# SmartMDCPrint.net
KiCad netlist of a schematic drawn in EAGLE
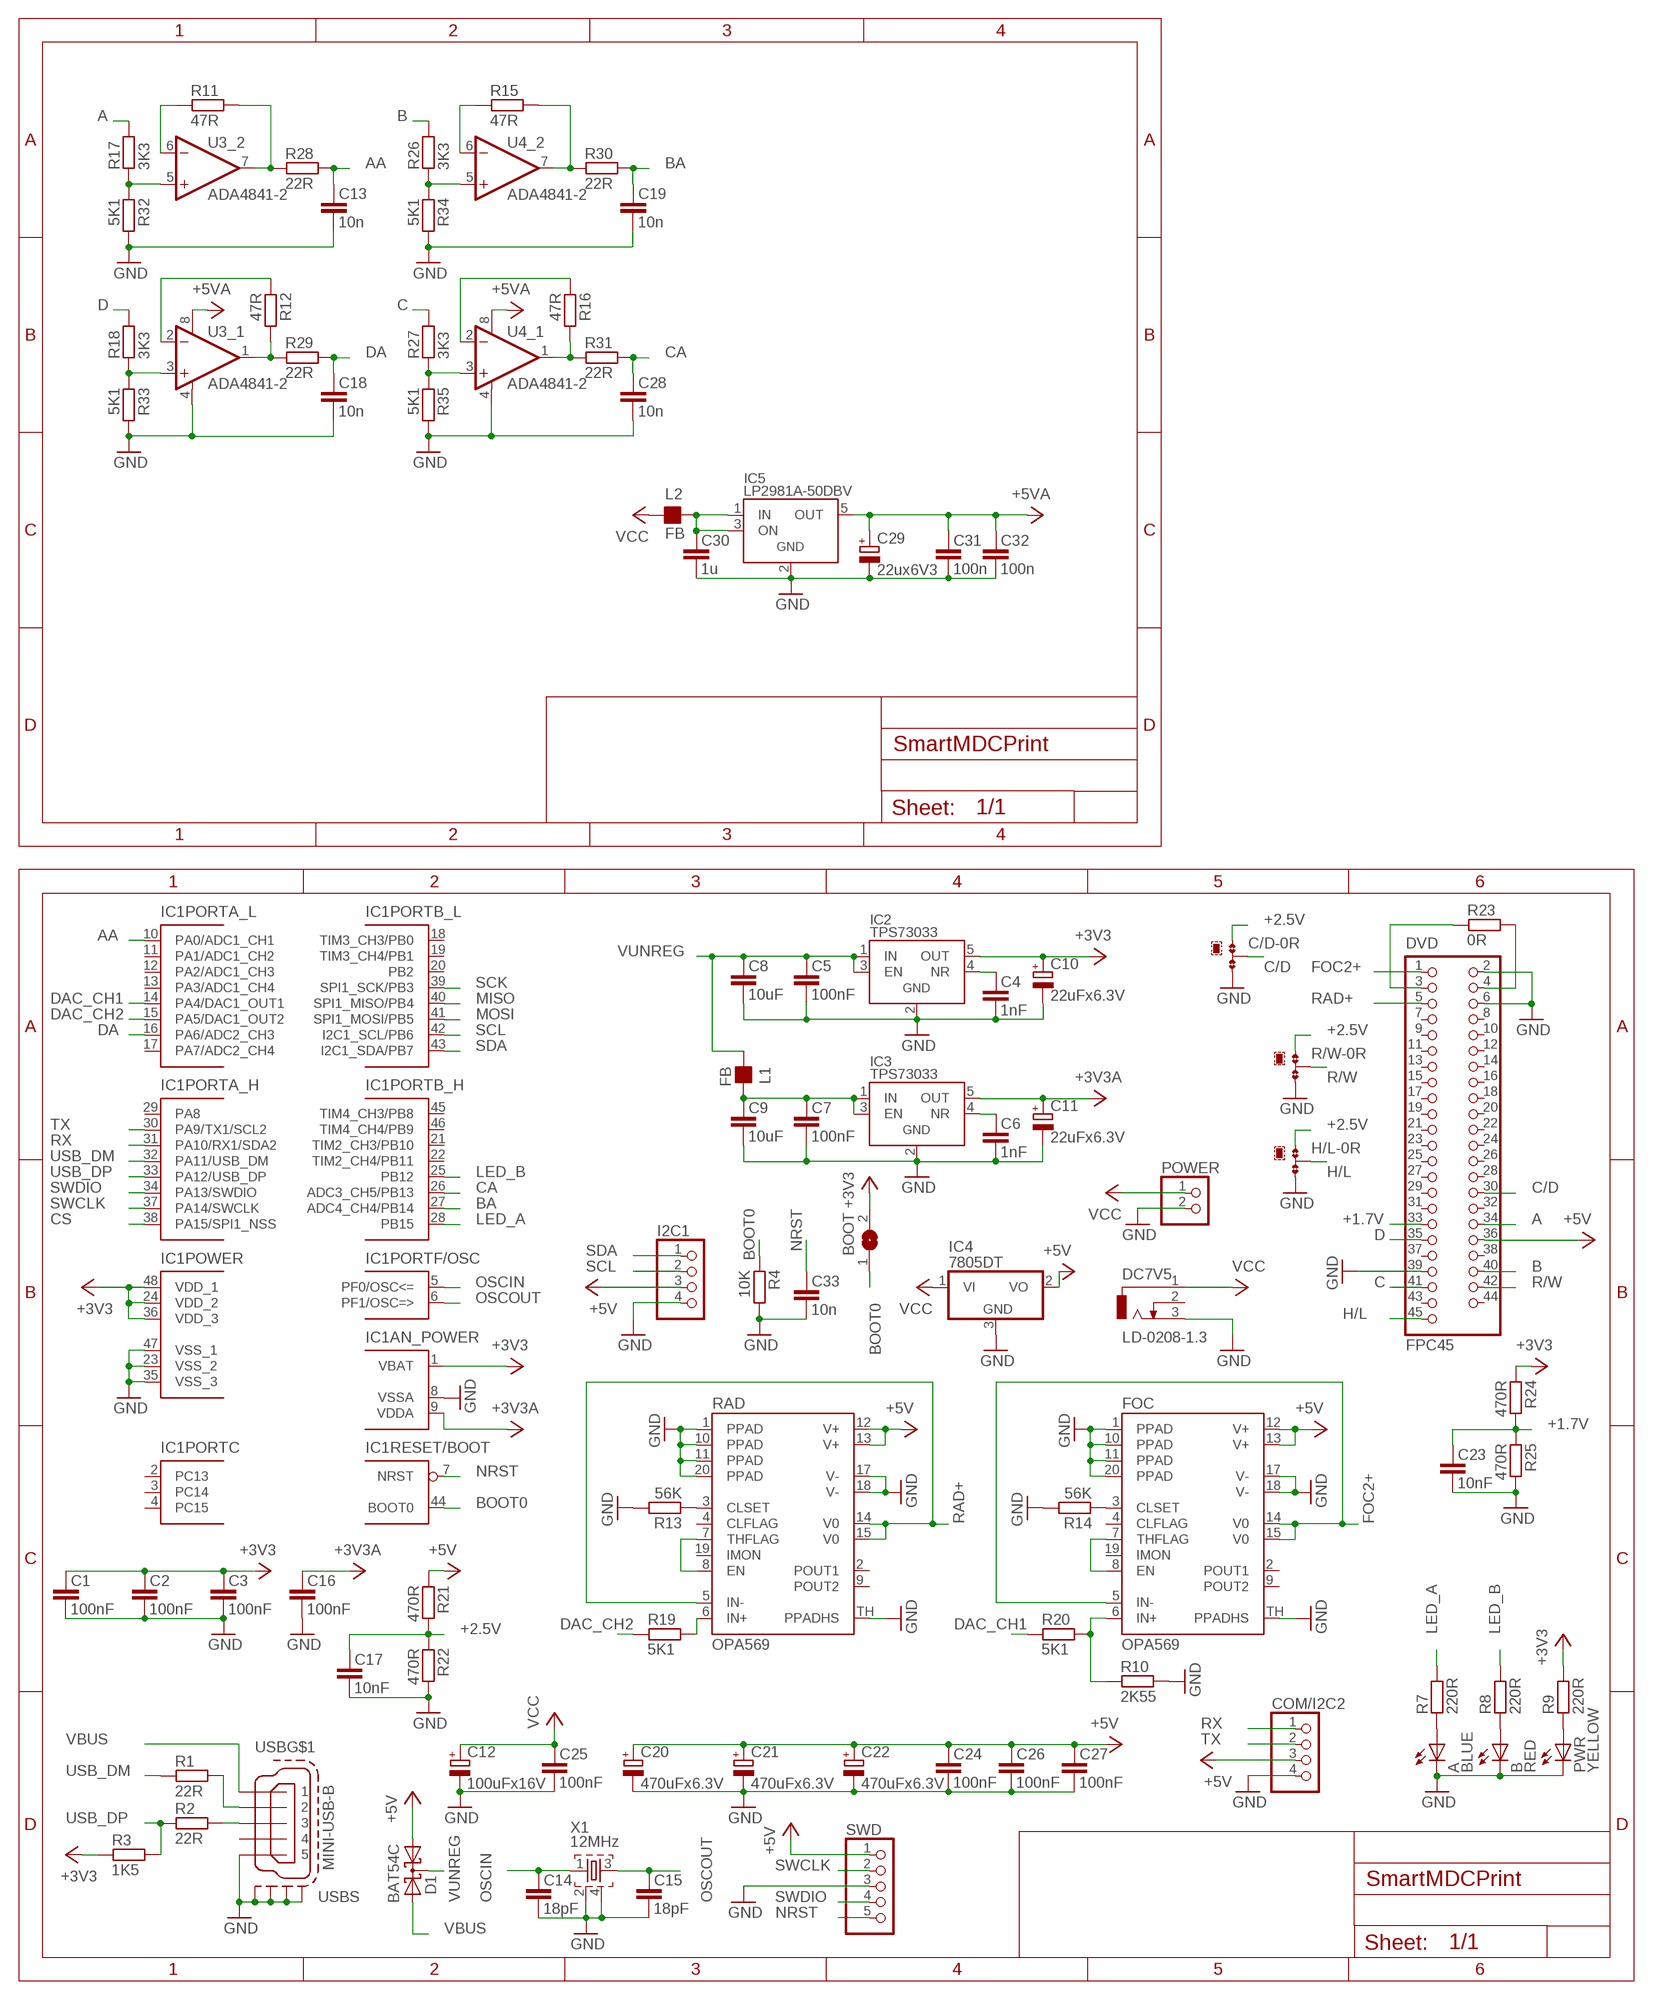
[diagram p0: schematic, sheet 1]

(export (version "E")
  (design (tool "Eeschema 10.0.6"))
  (components
    (comp (ref "A")
      (value "BLUE")
      (footprint "eagle-import:CHIPLED_0805")
      (libsource (lib "eagle-import") (part "LEDCHIPLED_0805"))
    )
    (comp (ref "B")
      (value "RED")
      (footprint "eagle-import:CHIPLED_0805")
      (libsource (lib "eagle-import") (part "LEDCHIPLED_0805"))
    )
    (comp (ref "BOOT")
      (value "SJ")
      (footprint "eagle-import:SJ")
      (libsource (lib "eagle-import") (part "SJ"))
    )
    (comp (ref "C/D")
      (value "0R-JUMPA")
      (footprint "eagle-import:A0R-JMP")
      (libsource (lib "eagle-import") (part "0R-JUMPA"))
    )
    (comp (ref "C1")
      (value "100nF")
      (footprint "eagle-import:C0603G")
      (libsource (lib "eagle-import") (part "C_EU_C0603G"))
    )
    (comp (ref "C2")
      (value "100nF")
      (footprint "eagle-import:C0603G")
      (libsource (lib "eagle-import") (part "C_EU_C0603G"))
    )
    (comp (ref "C3")
      (value "100nF")
      (footprint "eagle-import:C0603G")
      (libsource (lib "eagle-import") (part "C_EU_C0603G"))
    )
    (comp (ref "C4")
      (value "1nF")
      (footprint "eagle-import:C0603G")
      (libsource (lib "eagle-import") (part "C_EU_C0603G"))
    )
    (comp (ref "C5")
      (value "100nF")
      (footprint "eagle-import:C0603G")
      (libsource (lib "eagle-import") (part "C_EU_C0603G"))
    )
    (comp (ref "C6")
      (value "1nF")
      (footprint "eagle-import:C0603G")
      (libsource (lib "eagle-import") (part "C_EU_C0603G"))
    )
    (comp (ref "C7")
      (value "100nF")
      (footprint "eagle-import:C0603G")
      (libsource (lib "eagle-import") (part "C_EU_C0603G"))
    )
    (comp (ref "C8")
      (value "10uF")
      (footprint "eagle-import:C0805")
      (libsource (lib "eagle-import") (part "C_EU_C0805"))
    )
    (comp (ref "C9")
      (value "10uF")
      (footprint "eagle-import:C0805")
      (libsource (lib "eagle-import") (part "C_EU_C0805"))
    )
    (comp (ref "C10")
      (value "22uFx6.3V")
      (footprint "eagle-import:SMC_A")
      (libsource (lib "eagle-import") (part "CPOL-EUSMCA"))
    )
    (comp (ref "C11")
      (value "22uFx6.3V")
      (footprint "eagle-import:SMC_A")
      (libsource (lib "eagle-import") (part "CPOL-EUSMCA"))
    )
    (comp (ref "C12")
      (value "100uFx16V")
      (footprint "eagle-import:E2,5-7")
      (libsource (lib "eagle-import") (part "CPOL-EUE2.5-7"))
    )
    (comp (ref "C13")
      (value "10n")
      (footprint "eagle-import:C0603G")
      (libsource (lib "eagle-import") (part "C_EU_C0603G"))
    )
    (comp (ref "C14")
      (value "18pF")
      (footprint "eagle-import:C0603G")
      (libsource (lib "eagle-import") (part "C_EU_C0603G"))
    )
    (comp (ref "C15")
      (value "18pF")
      (footprint "eagle-import:C0603G")
      (libsource (lib "eagle-import") (part "C_EU_C0603G"))
    )
    (comp (ref "C16")
      (value "100nF")
      (footprint "eagle-import:C0603G")
      (libsource (lib "eagle-import") (part "C_EU_C0603G"))
    )
    (comp (ref "C17")
      (value "10nF")
      (footprint "eagle-import:C0603G")
      (libsource (lib "eagle-import") (part "C_EU_C0603G"))
    )
    (comp (ref "C18")
      (value "10n")
      (footprint "eagle-import:C0603G")
      (libsource (lib "eagle-import") (part "C_EU_C0603G"))
    )
    (comp (ref "C19")
      (value "10n")
      (footprint "eagle-import:C0603G")
      (libsource (lib "eagle-import") (part "C_EU_C0603G"))
    )
    (comp (ref "C20")
      (value "470uFx6.3V")
      (footprint "eagle-import:SMC_D")
      (libsource (lib "eagle-import") (part "CPOL-EUSMCD"))
    )
    (comp (ref "C21")
      (value "470uFx6.3V")
      (footprint "eagle-import:SMC_D")
      (libsource (lib "eagle-import") (part "CPOL-EUSMCD"))
    )
    (comp (ref "C22")
      (value "470uFx6.3V")
      (footprint "eagle-import:SMC_D")
      (libsource (lib "eagle-import") (part "CPOL-EUSMCD"))
    )
    (comp (ref "C23")
      (value "10nF")
      (footprint "eagle-import:C0603G")
      (libsource (lib "eagle-import") (part "C_EU_C0603G"))
    )
    (comp (ref "C24")
      (value "100nF")
      (footprint "eagle-import:C0603G")
      (libsource (lib "eagle-import") (part "C_EU_C0603G"))
    )
    (comp (ref "C25")
      (value "100nF")
      (footprint "eagle-import:C0603G")
      (libsource (lib "eagle-import") (part "C_EU_C0603G"))
    )
    (comp (ref "C26")
      (value "100nF")
      (footprint "eagle-import:C0603G")
      (libsource (lib "eagle-import") (part "C_EU_C0603G"))
    )
    (comp (ref "C27")
      (value "100nF")
      (footprint "eagle-import:C0603G")
      (libsource (lib "eagle-import") (part "C_EU_C0603G"))
    )
    (comp (ref "C28")
      (value "10n")
      (footprint "eagle-import:C0603G")
      (libsource (lib "eagle-import") (part "C_EU_C0603G"))
    )
    (comp (ref "C29")
      (value "22ux6V3")
      (footprint "eagle-import:SMC_A")
      (libsource (lib "eagle-import") (part "CPOL-EUSMCA"))
    )
    (comp (ref "C30")
      (value "1u")
      (footprint "eagle-import:C0603G")
      (libsource (lib "eagle-import") (part "C_EU_C0603G"))
    )
    (comp (ref "C31")
      (value "100n")
      (footprint "eagle-import:C0603G")
      (libsource (lib "eagle-import") (part "C_EU_C0603G"))
    )
    (comp (ref "C32")
      (value "100n")
      (footprint "eagle-import:C0603G")
      (libsource (lib "eagle-import") (part "C_EU_C0603G"))
    )
    (comp (ref "C33")
      (value "10n")
      (footprint "eagle-import:C0603G")
      (libsource (lib "eagle-import") (part "C_EU_C0603G"))
    )
    (comp (ref "COM/I2C2")
      (value "PINHD-1X4")
      (footprint "eagle-import:1X04")
      (libsource (lib "eagle-import") (part "PINHD-1X4"))
    )
    (comp (ref "D1")
      (value "BAT54C")
      (footprint "eagle-import:SOT23")
      (libsource (lib "eagle-import") (part "BAT54C"))
    )
    (comp (ref "DC7V5")
      (value "LD-0208-1.3")
      (footprint "eagle-import:LD-0208")
      (libsource (lib "eagle-import") (part "LD-0208-1.3"))
    )
    (comp (ref "DVD")
      (value "FPC45")
      (footprint "eagle-import:FPC45")
      (libsource (lib "eagle-import") (part "CON-FPC45"))
    )
    (comp (ref "FOC")
      (value "OPA569")
      (footprint "eagle-import:SO-20")
      (libsource (lib "eagle-import") (part "OPA569"))
    )
    (comp (ref "H/L")
      (value "0R-JUMPA")
      (footprint "eagle-import:A0R-JMP")
      (libsource (lib "eagle-import") (part "0R-JUMPA"))
    )
    (comp (ref "I2C1")
      (value "PINHD-1X4")
      (footprint "eagle-import:1X04")
      (libsource (lib "eagle-import") (part "PINHD-1X4"))
    )
    (comp (ref "IC1")
      (value "STM32F303CCT6")
      (footprint "eagle-import:LQFP48")
      (libsource (lib "eagle-import") (part "STM32F303CXT6"))
    )
    (comp (ref "IC2")
      (value "TPS73033")
      (footprint "eagle-import:SOT23-5")
      (libsource (lib "eagle-import") (part "TPS769XX"))
    )
    (comp (ref "IC3")
      (value "TPS73033")
      (footprint "eagle-import:SOT23-5")
      (libsource (lib "eagle-import") (part "TPS769XX"))
    )
    (comp (ref "IC4")
      (value "7805DT")
      (footprint "eagle-import:TO252")
      (libsource (lib "eagle-import") (part "78DT05"))
    )
    (comp (ref "IC5")
      (value "LP2981A-50DBV")
      (footprint "eagle-import:SOT23-5")
      (libsource (lib "eagle-import") (part "LP2981A-50DBV"))
    )
    (comp (ref "L1")
      (value "FB")
      (footprint "eagle-import:L0603")
      (libsource (lib "eagle-import") (part "FB_0603"))
    )
    (comp (ref "L2")
      (value "FB")
      (footprint "eagle-import:L0603")
      (libsource (lib "eagle-import") (part "FB_0603"))
    )
    (comp (ref "POWER")
      (value "PINHD-1X2")
      (footprint "eagle-import:1X02")
      (libsource (lib "eagle-import") (part "PINHD-1X2"))
    )
    (comp (ref "PWR")
      (value "YELLOW")
      (footprint "eagle-import:CHIPLED_0805")
      (libsource (lib "eagle-import") (part "LEDCHIPLED_0805"))
    )
    (comp (ref "R/W")
      (value "0R-JUMPA")
      (footprint "eagle-import:A0R-JMP")
      (libsource (lib "eagle-import") (part "0R-JUMPA"))
    )
    (comp (ref "R1")
      (value "22R")
      (footprint "eagle-import:R0603")
      (libsource (lib "eagle-import") (part "R_EU_R0603"))
    )
    (comp (ref "R2")
      (value "22R")
      (footprint "eagle-import:R0603")
      (libsource (lib "eagle-import") (part "R_EU_R0603"))
    )
    (comp (ref "R3")
      (value "1K5")
      (footprint "eagle-import:R0603")
      (libsource (lib "eagle-import") (part "R_EU_R0603"))
    )
    (comp (ref "R4")
      (value "10K")
      (footprint "eagle-import:R0603G")
      (libsource (lib "eagle-import") (part "R_EU_R0603G"))
    )
    (comp (ref "R7")
      (value "220R")
      (footprint "eagle-import:R0603")
      (libsource (lib "eagle-import") (part "R_EU_R0603"))
    )
    (comp (ref "R8")
      (value "220R")
      (footprint "eagle-import:R0603")
      (libsource (lib "eagle-import") (part "R_EU_R0603"))
    )
    (comp (ref "R9")
      (value "220R")
      (footprint "eagle-import:R0603")
      (libsource (lib "eagle-import") (part "R_EU_R0603"))
    )
    (comp (ref "R10")
      (value "2K55")
      (footprint "eagle-import:R0603G")
      (libsource (lib "eagle-import") (part "R_EU_R0603G"))
    )
    (comp (ref "R11")
      (value "47R")
      (footprint "eagle-import:R0603")
      (libsource (lib "eagle-import") (part "R_EU_R0603"))
    )
    (comp (ref "R12")
      (value "47R")
      (footprint "eagle-import:R0603")
      (libsource (lib "eagle-import") (part "R_EU_R0603"))
    )
    (comp (ref "R13")
      (value "56K")
      (footprint "eagle-import:R0603G")
      (libsource (lib "eagle-import") (part "R_EU_R0603G"))
    )
    (comp (ref "R14")
      (value "56K")
      (footprint "eagle-import:R0603G")
      (libsource (lib "eagle-import") (part "R_EU_R0603G"))
    )
    (comp (ref "R15")
      (value "47R")
      (footprint "eagle-import:R0603")
      (libsource (lib "eagle-import") (part "R_EU_R0603"))
    )
    (comp (ref "R16")
      (value "47R")
      (footprint "eagle-import:R0603")
      (libsource (lib "eagle-import") (part "R_EU_R0603"))
    )
    (comp (ref "R17")
      (value "3K3")
      (footprint "eagle-import:R0603")
      (libsource (lib "eagle-import") (part "R_EU_R0603"))
    )
    (comp (ref "R18")
      (value "3K3")
      (footprint "eagle-import:R0603")
      (libsource (lib "eagle-import") (part "R_EU_R0603"))
    )
    (comp (ref "R19")
      (value "5K1")
      (footprint "eagle-import:R0603")
      (libsource (lib "eagle-import") (part "R_EU_R0603"))
    )
    (comp (ref "R20")
      (value "5K1")
      (footprint "eagle-import:R0603")
      (libsource (lib "eagle-import") (part "R_EU_R0603"))
    )
    (comp (ref "R21")
      (value "470R")
      (footprint "eagle-import:R0603")
      (libsource (lib "eagle-import") (part "R_EU_R0603"))
    )
    (comp (ref "R22")
      (value "470R")
      (footprint "eagle-import:R0603G")
      (libsource (lib "eagle-import") (part "R_EU_R0603G"))
    )
    (comp (ref "R23")
      (value "0R")
      (footprint "eagle-import:R0603")
      (libsource (lib "eagle-import") (part "R_EU_R0603"))
    )
    (comp (ref "R24")
      (value "470R")
      (footprint "eagle-import:R0603")
      (libsource (lib "eagle-import") (part "R_EU_R0603"))
    )
    (comp (ref "R25")
      (value "470R")
      (footprint "eagle-import:R0603G")
      (libsource (lib "eagle-import") (part "R_EU_R0603G"))
    )
    (comp (ref "R26")
      (value "3K3")
      (footprint "eagle-import:R0603")
      (libsource (lib "eagle-import") (part "R_EU_R0603"))
    )
    (comp (ref "R27")
      (value "3K3")
      (footprint "eagle-import:R0603")
      (libsource (lib "eagle-import") (part "R_EU_R0603"))
    )
    (comp (ref "R28")
      (value "22R")
      (footprint "eagle-import:R0603")
      (libsource (lib "eagle-import") (part "R_EU_R0603"))
    )
    (comp (ref "R29")
      (value "22R")
      (footprint "eagle-import:R0603")
      (libsource (lib "eagle-import") (part "R_EU_R0603"))
    )
    (comp (ref "R30")
      (value "22R")
      (footprint "eagle-import:R0603")
      (libsource (lib "eagle-import") (part "R_EU_R0603"))
    )
    (comp (ref "R31")
      (value "22R")
      (footprint "eagle-import:R0603")
      (libsource (lib "eagle-import") (part "R_EU_R0603"))
    )
    (comp (ref "R32")
      (value "5K1")
      (footprint "eagle-import:R0603G")
      (libsource (lib "eagle-import") (part "R_EU_R0603G"))
    )
    (comp (ref "R33")
      (value "5K1")
      (footprint "eagle-import:R0603G")
      (libsource (lib "eagle-import") (part "R_EU_R0603G"))
    )
    (comp (ref "R34")
      (value "5K1")
      (footprint "eagle-import:R0603G")
      (libsource (lib "eagle-import") (part "R_EU_R0603G"))
    )
    (comp (ref "R35")
      (value "5K1")
      (footprint "eagle-import:R0603G")
      (libsource (lib "eagle-import") (part "R_EU_R0603G"))
    )
    (comp (ref "RAD")
      (value "OPA569")
      (footprint "eagle-import:SO-20")
      (libsource (lib "eagle-import") (part "OPA569"))
    )
    (comp (ref "SWD")
      (value "PINHD-1X5")
      (footprint "eagle-import:1X05")
      (libsource (lib "eagle-import") (part "PINHD-1X5"))
    )
    (comp (ref "U3")
      (value "ADA4841-2")
      (footprint "eagle-import:SOIC-8")
      (libsource (lib "eagle-import") (part "ADA4841-2"))
    )
    (comp (ref "U4")
      (value "ADA4841-2")
      (footprint "eagle-import:SOIC-8")
      (libsource (lib "eagle-import") (part "ADA4841-2"))
    )
    (comp (ref "USB")
      (value "MINI-USB-B")
      (footprint "eagle-import:32005-201")
      (libsource (lib "eagle-import") (part "MINI-USB-SCHIELD-32005-201"))
    )
    (comp (ref "X1")
      (value "12MHz")
      (footprint "eagle-import:ABMM2")
      (libsource (lib "eagle-import") (part "ABMM2"))
    )
  )
  (nets
    (net (code "1") (name "+3V3") (class "Default")
      (node (ref "BOOT") (pin "2") (pinfunction "2_2") (pintype "passive"))
      (node (ref "C1") (pin "1") (pinfunction "1_1") (pintype "passive"))
      (node (ref "C10") (pin "+") (pinfunction "+_+") (pintype "passive"))
      (node (ref "C2") (pin "1") (pinfunction "1_1") (pintype "passive"))
      (node (ref "C3") (pin "1") (pinfunction "1_1") (pintype "passive"))
      (node (ref "IC1") (pin "1") (pinfunction "VBAT_1") (pintype "power_in"))
      (node (ref "IC1") (pin "24") (pinfunction "VDD_2_24") (pintype "power_in"))
      (node (ref "IC1") (pin "36") (pinfunction "VDD_3_36") (pintype "power_in"))
      (node (ref "IC1") (pin "48") (pinfunction "VDD_1_48") (pintype "power_in"))
      (node (ref "IC2") (pin "5") (pinfunction "OUT_5") (pintype "power_in"))
      (node (ref "R24") (pin "1") (pinfunction "1_1") (pintype "passive"))
      (node (ref "R3") (pin "1") (pinfunction "1_1") (pintype "passive"))
      (node (ref "R9") (pin "2") (pinfunction "2_2") (pintype "passive"))
    )
    (net (code "2") (name "+3V3A") (class "Default")
      (node (ref "C11") (pin "+") (pinfunction "+_+") (pintype "passive"))
      (node (ref "C16") (pin "1") (pinfunction "1_1") (pintype "passive"))
      (node (ref "IC1") (pin "9") (pinfunction "VDDA_9") (pintype "power_in"))
      (node (ref "IC3") (pin "5") (pinfunction "OUT_5") (pintype "power_in"))
    )
    (net (code "3") (name "+5V") (class "Default")
      (node (ref "C20") (pin "+") (pinfunction "+_+") (pintype "passive"))
      (node (ref "C21") (pin "+") (pinfunction "+_+") (pintype "passive"))
      (node (ref "C22") (pin "+") (pinfunction "+_+") (pintype "passive"))
      (node (ref "C24") (pin "1") (pinfunction "1_1") (pintype "passive"))
      (node (ref "C26") (pin "1") (pinfunction "1_1") (pintype "passive"))
      (node (ref "C27") (pin "1") (pinfunction "1_1") (pintype "passive"))
      (node (ref "COM/I2C2") (pin "3") (pinfunction "3_3") (pintype "passive"))
      (node (ref "D1") (pin "1") (pinfunction "A1_1") (pintype "passive"))
      (node (ref "DVD") (pin "36") (pinfunction "36_36") (pintype "passive"))
      (node (ref "FOC") (pin "12") (pinfunction "V+_12") (pintype "bidirectional"))
      (node (ref "FOC") (pin "13") (pinfunction "V+_13") (pintype "bidirectional"))
      (node (ref "I2C1") (pin "3") (pinfunction "3_3") (pintype "passive"))
      (node (ref "IC4") (pin "2") (pinfunction "VO_2") (pintype "passive"))
      (node (ref "R21") (pin "1") (pinfunction "1_1") (pintype "passive"))
      (node (ref "RAD") (pin "12") (pinfunction "V+_12") (pintype "bidirectional"))
      (node (ref "RAD") (pin "13") (pinfunction "V+_13") (pintype "bidirectional"))
      (node (ref "SWD") (pin "1") (pinfunction "1_1") (pintype "passive"))
    )
    (net (code "4") (name "+5VA") (class "Default")
      (node (ref "C29") (pin "+") (pinfunction "+_+") (pintype "passive"))
      (node (ref "C31") (pin "1") (pinfunction "1_1") (pintype "passive"))
      (node (ref "C32") (pin "1") (pinfunction "1_1") (pintype "passive"))
      (node (ref "IC5") (pin "5") (pinfunction "OUT_5") (pintype "power_in"))
      (node (ref "U3") (pin "8") (pinfunction "V+_8") (pintype "power_in"))
      (node (ref "U4") (pin "8") (pinfunction "V+_8") (pintype "power_in"))
    )
    (net (code "5") (name "/+1.7V") (class "Default")
      (node (ref "C23") (pin "1") (pinfunction "1_1") (pintype "passive"))
      (node (ref "DVD") (pin "33") (pinfunction "33_33") (pintype "passive"))
      (node (ref "R24") (pin "2") (pinfunction "2_2") (pintype "passive"))
      (node (ref "R25") (pin "1") (pinfunction "1_1") (pintype "passive"))
    )
    (net (code "6") (name "/+2.5V") (class "Default")
      (node (ref "C/D") (pin "1") (pinfunction "1_1") (pintype "passive"))
      (node (ref "C17") (pin "1") (pinfunction "1_1") (pintype "passive"))
      (node (ref "H/L") (pin "1") (pinfunction "1_1") (pintype "passive"))
      (node (ref "R/W") (pin "1") (pinfunction "1_1") (pintype "passive"))
      (node (ref "R21") (pin "2") (pinfunction "2_2") (pintype "passive"))
      (node (ref "R22") (pin "1") (pinfunction "1_1") (pintype "passive"))
    )
    (net (code "7") (name "/A") (class "Default")
      (node (ref "DVD") (pin "34") (pinfunction "34_34") (pintype "passive"))
      (node (ref "R17") (pin "2") (pinfunction "2_2") (pintype "passive"))
    )
    (net (code "8") (name "/AA") (class "Default")
      (node (ref "C13") (pin "1") (pinfunction "1_1") (pintype "passive"))
      (node (ref "IC1") (pin "10") (pinfunction "PA0/ADC1_CH1_10") (pintype "bidirectional"))
      (node (ref "R28") (pin "2") (pinfunction "2_2") (pintype "passive"))
    )
    (net (code "9") (name "/B") (class "Default")
      (node (ref "DVD") (pin "40") (pinfunction "40_40") (pintype "passive"))
      (node (ref "R26") (pin "2") (pinfunction "2_2") (pintype "passive"))
    )
    (net (code "10") (name "/BA") (class "Default")
      (node (ref "C19") (pin "1") (pinfunction "1_1") (pintype "passive"))
      (node (ref "IC1") (pin "27") (pinfunction "ADC4_CH4/PB14_27") (pintype "bidirectional"))
      (node (ref "R30") (pin "2") (pinfunction "2_2") (pintype "passive"))
    )
    (net (code "11") (name "/BOOT0") (class "Default")
      (node (ref "BOOT") (pin "1") (pinfunction "1_1") (pintype "passive"))
      (node (ref "IC1") (pin "44") (pinfunction "BOOT0_44") (pintype "input"))
      (node (ref "R4") (pin "1") (pinfunction "1_1") (pintype "passive"))
    )
    (net (code "12") (name "/C") (class "Default")
      (node (ref "DVD") (pin "41") (pinfunction "41_41") (pintype "passive"))
      (node (ref "R27") (pin "2") (pinfunction "2_2") (pintype "passive"))
    )
    (net (code "13") (name "/CA") (class "Default")
      (node (ref "C28") (pin "1") (pinfunction "1_1") (pintype "passive"))
      (node (ref "IC1") (pin "26") (pinfunction "ADC3_CH5/PB13_26") (pintype "bidirectional"))
      (node (ref "R31") (pin "2") (pinfunction "2_2") (pintype "passive"))
    )
    (net (code "14") (name "/CS") (class "Default")
      (node (ref "IC1") (pin "38") (pinfunction "PA15/SPI1_NSS_38") (pintype "bidirectional"))
    )
    (net (code "15") (name "/C{slash}D") (class "Default")
      (node (ref "C/D") (pin "2") (pinfunction "2_2") (pintype "passive"))
      (node (ref "DVD") (pin "30") (pinfunction "30_30") (pintype "passive"))
    )
    (net (code "16") (name "/D") (class "Default")
      (node (ref "DVD") (pin "35") (pinfunction "35_35") (pintype "passive"))
      (node (ref "R18") (pin "2") (pinfunction "2_2") (pintype "passive"))
    )
    (net (code "17") (name "/DA") (class "Default")
      (node (ref "C18") (pin "1") (pinfunction "1_1") (pintype "passive"))
      (node (ref "IC1") (pin "16") (pinfunction "PA6/ADC2_CH3_16") (pintype "bidirectional"))
      (node (ref "R29") (pin "2") (pinfunction "2_2") (pintype "passive"))
    )
    (net (code "18") (name "/DAC_CH1") (class "Default")
      (node (ref "IC1") (pin "14") (pinfunction "PA4/DAC1_OUT1_14") (pintype "bidirectional"))
      (node (ref "R20") (pin "1") (pinfunction "1_1") (pintype "passive"))
    )
    (net (code "19") (name "/DAC_CH2") (class "Default")
      (node (ref "IC1") (pin "15") (pinfunction "PA5/DAC1_OUT2_15") (pintype "bidirectional"))
      (node (ref "R19") (pin "1") (pinfunction "1_1") (pintype "passive"))
    )
    (net (code "20") (name "/FOC2+") (class "Default")
      (node (ref "DVD") (pin "1") (pinfunction "1_1") (pintype "passive"))
      (node (ref "FOC") (pin "14") (pinfunction "V0_14") (pintype "bidirectional"))
      (node (ref "FOC") (pin "15") (pinfunction "V0_15") (pintype "bidirectional"))
      (node (ref "FOC") (pin "5") (pinfunction "IN-_5") (pintype "bidirectional"))
    )
    (net (code "21") (name "/H{slash}L") (class "Default")
      (node (ref "DVD") (pin "45") (pinfunction "45_45") (pintype "passive"))
      (node (ref "H/L") (pin "2") (pinfunction "2_2") (pintype "passive"))
    )
    (net (code "22") (name "/LED_A") (class "Default")
      (node (ref "IC1") (pin "28") (pinfunction "PB15_28") (pintype "bidirectional"))
      (node (ref "R7") (pin "2") (pinfunction "2_2") (pintype "passive"))
    )
    (net (code "23") (name "/LED_B") (class "Default")
      (node (ref "IC1") (pin "25") (pinfunction "PB12_25") (pintype "bidirectional"))
      (node (ref "R8") (pin "2") (pinfunction "2_2") (pintype "passive"))
    )
    (net (code "24") (name "/MISO") (class "Default")
      (node (ref "IC1") (pin "40") (pinfunction "SPI1_MISO/PB4_40") (pintype "bidirectional"))
    )
    (net (code "25") (name "/MOSI") (class "Default")
      (node (ref "IC1") (pin "41") (pinfunction "SPI1_MOSI/PB5_41") (pintype "bidirectional"))
    )
    (net (code "26") (name "/NRST") (class "Default")
      (node (ref "C33") (pin "1") (pinfunction "1_1") (pintype "passive"))
      (node (ref "IC1") (pin "7") (pinfunction "NRST_7") (pintype "input"))
      (node (ref "SWD") (pin "5") (pinfunction "5_5") (pintype "passive"))
    )
    (net (code "27") (name "/OSCIN") (class "Default")
      (node (ref "C14") (pin "1") (pinfunction "1_1") (pintype "passive"))
      (node (ref "IC1") (pin "5") (pinfunction "PF0/OSC<=_5") (pintype "bidirectional"))
      (node (ref "X1") (pin "1") (pinfunction "1_1") (pintype "passive"))
    )
    (net (code "28") (name "/OSCOUT") (class "Default")
      (node (ref "C15") (pin "1") (pinfunction "1_1") (pintype "passive"))
      (node (ref "IC1") (pin "6") (pinfunction "PF1/OSC=>_6") (pintype "bidirectional"))
      (node (ref "X1") (pin "3") (pinfunction "3_3") (pintype "passive"))
    )
    (net (code "29") (name "/RAD+") (class "Default")
      (node (ref "DVD") (pin "5") (pinfunction "5_5") (pintype "passive"))
      (node (ref "RAD") (pin "14") (pinfunction "V0_14") (pintype "bidirectional"))
      (node (ref "RAD") (pin "15") (pinfunction "V0_15") (pintype "bidirectional"))
      (node (ref "RAD") (pin "5") (pinfunction "IN-_5") (pintype "bidirectional"))
    )
    (net (code "30") (name "/RX") (class "Default")
      (node (ref "COM/I2C2") (pin "1") (pinfunction "1_1") (pintype "passive"))
      (node (ref "IC1") (pin "31") (pinfunction "PA10/RX1/SDA2_31") (pintype "bidirectional"))
    )
    (net (code "31") (name "/R{slash}W") (class "Default")
      (node (ref "DVD") (pin "42") (pinfunction "42_42") (pintype "passive"))
      (node (ref "R/W") (pin "2") (pinfunction "2_2") (pintype "passive"))
    )
    (net (code "32") (name "/SCK") (class "Default")
      (node (ref "IC1") (pin "39") (pinfunction "SPI1_SCK/PB3_39") (pintype "bidirectional"))
    )
    (net (code "33") (name "/SCL") (class "Default")
      (node (ref "I2C1") (pin "2") (pinfunction "2_2") (pintype "passive"))
      (node (ref "IC1") (pin "42") (pinfunction "I2C1_SCL/PB6_42") (pintype "bidirectional"))
    )
    (net (code "34") (name "/SDA") (class "Default")
      (node (ref "I2C1") (pin "1") (pinfunction "1_1") (pintype "passive"))
      (node (ref "IC1") (pin "43") (pinfunction "I2C1_SDA/PB7_43") (pintype "bidirectional"))
    )
    (net (code "35") (name "/SWCLK") (class "Default")
      (node (ref "IC1") (pin "37") (pinfunction "PA14/SWCLK_37") (pintype "bidirectional"))
      (node (ref "SWD") (pin "2") (pinfunction "2_2") (pintype "passive"))
    )
    (net (code "36") (name "/SWDIO") (class "Default")
      (node (ref "IC1") (pin "34") (pinfunction "PA13/SWDIO_34") (pintype "bidirectional"))
      (node (ref "SWD") (pin "4") (pinfunction "4_4") (pintype "passive"))
    )
    (net (code "37") (name "/TX") (class "Default")
      (node (ref "COM/I2C2") (pin "2") (pinfunction "2_2") (pintype "passive"))
      (node (ref "IC1") (pin "30") (pinfunction "PA9/TX1/SCL2_30") (pintype "bidirectional"))
    )
    (net (code "38") (name "/USB_DM") (class "Default")
      (node (ref "IC1") (pin "32") (pinfunction "PA11/USB_DM_32") (pintype "bidirectional"))
      (node (ref "R1") (pin "1") (pinfunction "1_1") (pintype "passive"))
    )
    (net (code "39") (name "/USB_DP") (class "Default")
      (node (ref "IC1") (pin "33") (pinfunction "PA12/USB_DP_33") (pintype "bidirectional"))
      (node (ref "R2") (pin "1") (pinfunction "1_1") (pintype "passive"))
      (node (ref "R3") (pin "2") (pinfunction "2_2") (pintype "passive"))
    )
    (net (code "40") (name "/VBUS") (class "Default")
      (node (ref "D1") (pin "2") (pinfunction "A2_2") (pintype "passive"))
      (node (ref "USB") (pin "1") (pinfunction "1_1") (pintype "passive"))
    )
    (net (code "41") (name "/VUNREG") (class "Default")
      (node (ref "C5") (pin "1") (pinfunction "1_1") (pintype "passive"))
      (node (ref "C8") (pin "1") (pinfunction "1_1") (pintype "passive"))
      (node (ref "D1") (pin "3") (pinfunction "CC_3") (pintype "passive"))
      (node (ref "IC2") (pin "1") (pinfunction "IN_1") (pintype "power_in"))
      (node (ref "IC2") (pin "3") (pinfunction "EN_3") (pintype "passive"))
      (node (ref "L1") (pin "1") (pinfunction "1_1") (pintype "passive"))
    )
    (net (code "42") (name "GND") (class "Default")
      (node (ref "A") (pin "C") (pinfunction "C_C") (pintype "passive"))
      (node (ref "B") (pin "C") (pinfunction "C_C") (pintype "passive"))
      (node (ref "C/D") (pin "3") (pinfunction "3_3") (pintype "passive"))
      (node (ref "C1") (pin "2") (pinfunction "2_2") (pintype "passive"))
      (node (ref "C10") (pin "-") (pinfunction "-_-") (pintype "passive"))
      (node (ref "C11") (pin "-") (pinfunction "-_-") (pintype "passive"))
      (node (ref "C12") (pin "-") (pinfunction "-_-") (pintype "passive"))
      (node (ref "C13") (pin "2") (pinfunction "2_2") (pintype "passive"))
      (node (ref "C14") (pin "2") (pinfunction "2_2") (pintype "passive"))
      (node (ref "C15") (pin "2") (pinfunction "2_2") (pintype "passive"))
      (node (ref "C16") (pin "2") (pinfunction "2_2") (pintype "passive"))
      (node (ref "C17") (pin "2") (pinfunction "2_2") (pintype "passive"))
      (node (ref "C18") (pin "2") (pinfunction "2_2") (pintype "passive"))
      (node (ref "C19") (pin "2") (pinfunction "2_2") (pintype "passive"))
      (node (ref "C2") (pin "2") (pinfunction "2_2") (pintype "passive"))
      (node (ref "C20") (pin "-") (pinfunction "-_-") (pintype "passive"))
      (node (ref "C21") (pin "-") (pinfunction "-_-") (pintype "passive"))
      (node (ref "C22") (pin "-") (pinfunction "-_-") (pintype "passive"))
      (node (ref "C23") (pin "2") (pinfunction "2_2") (pintype "passive"))
      (node (ref "C24") (pin "2") (pinfunction "2_2") (pintype "passive"))
      (node (ref "C25") (pin "2") (pinfunction "2_2") (pintype "passive"))
      (node (ref "C26") (pin "2") (pinfunction "2_2") (pintype "passive"))
      (node (ref "C27") (pin "2") (pinfunction "2_2") (pintype "passive"))
      (node (ref "C28") (pin "2") (pinfunction "2_2") (pintype "passive"))
      (node (ref "C29") (pin "-") (pinfunction "-_-") (pintype "passive"))
      (node (ref "C3") (pin "2") (pinfunction "2_2") (pintype "passive"))
      (node (ref "C30") (pin "2") (pinfunction "2_2") (pintype "passive"))
      (node (ref "C31") (pin "2") (pinfunction "2_2") (pintype "passive"))
      (node (ref "C32") (pin "2") (pinfunction "2_2") (pintype "passive"))
      (node (ref "C33") (pin "2") (pinfunction "2_2") (pintype "passive"))
      (node (ref "C4") (pin "2") (pinfunction "2_2") (pintype "passive"))
      (node (ref "C5") (pin "2") (pinfunction "2_2") (pintype "passive"))
      (node (ref "C6") (pin "2") (pinfunction "2_2") (pintype "passive"))
      (node (ref "C7") (pin "2") (pinfunction "2_2") (pintype "passive"))
      (node (ref "C8") (pin "2") (pinfunction "2_2") (pintype "passive"))
      (node (ref "C9") (pin "2") (pinfunction "2_2") (pintype "passive"))
      (node (ref "COM/I2C2") (pin "4") (pinfunction "4_4") (pintype "passive"))
      (node (ref "DC7V5") (pin "3") (pinfunction "3_3") (pintype "passive"))
      (node (ref "DVD") (pin "2") (pinfunction "2_2") (pintype "passive"))
      (node (ref "DVD") (pin "39") (pinfunction "39_39") (pintype "passive"))
      (node (ref "DVD") (pin "6") (pinfunction "6_6") (pintype "passive"))
      (node (ref "FOC") (pin "1") (pinfunction "PPAD_1") (pintype "bidirectional"))
      (node (ref "FOC") (pin "10") (pinfunction "PPAD_10") (pintype "bidirectional"))
      (node (ref "FOC") (pin "11") (pinfunction "PPAD_11") (pintype "bidirectional"))
      (node (ref "FOC") (pin "17") (pinfunction "V-_17") (pintype "bidirectional"))
      (node (ref "FOC") (pin "18") (pinfunction "V-_18") (pintype "bidirectional"))
      (node (ref "FOC") (pin "20") (pinfunction "PPAD_20") (pintype "bidirectional"))
      (node (ref "FOC") (pin "TH") (pinfunction "PPADHS_TH") (pintype "bidirectional"))
      (node (ref "H/L") (pin "3") (pinfunction "3_3") (pintype "passive"))
      (node (ref "I2C1") (pin "4") (pinfunction "4_4") (pintype "passive"))
      (node (ref "IC1") (pin "23") (pinfunction "VSS_2_23") (pintype "power_in"))
      (node (ref "IC1") (pin "35") (pinfunction "VSS_3_35") (pintype "power_in"))
      (node (ref "IC1") (pin "47") (pinfunction "VSS_1_47") (pintype "power_in"))
      (node (ref "IC1") (pin "8") (pinfunction "VSSA_8") (pintype "power_in"))
      (node (ref "IC2") (pin "2") (pinfunction "GND_2") (pintype "power_in"))
      (node (ref "IC3") (pin "2") (pinfunction "GND_2") (pintype "power_in"))
      (node (ref "IC4") (pin "3") (pinfunction "GND_3") (pintype "passive"))
      (node (ref "IC5") (pin "2") (pinfunction "GND_2") (pintype "power_in"))
      (node (ref "POWER") (pin "2") (pinfunction "2_2") (pintype "passive"))
      (node (ref "PWR") (pin "C") (pinfunction "C_C") (pintype "passive"))
      (node (ref "R/W") (pin "3") (pinfunction "3_3") (pintype "passive"))
      (node (ref "R10") (pin "2") (pinfunction "2_2") (pintype "passive"))
      (node (ref "R13") (pin "2") (pinfunction "2_2") (pintype "passive"))
      (node (ref "R14") (pin "2") (pinfunction "2_2") (pintype "passive"))
      (node (ref "R22") (pin "2") (pinfunction "2_2") (pintype "passive"))
      (node (ref "R25") (pin "2") (pinfunction "2_2") (pintype "passive"))
      (node (ref "R32") (pin "2") (pinfunction "2_2") (pintype "passive"))
      (node (ref "R33") (pin "2") (pinfunction "2_2") (pintype "passive"))
      (node (ref "R34") (pin "2") (pinfunction "2_2") (pintype "passive"))
      (node (ref "R35") (pin "2") (pinfunction "2_2") (pintype "passive"))
      (node (ref "R4") (pin "2") (pinfunction "2_2") (pintype "passive"))
      (node (ref "RAD") (pin "1") (pinfunction "PPAD_1") (pintype "bidirectional"))
      (node (ref "RAD") (pin "10") (pinfunction "PPAD_10") (pintype "bidirectional"))
      (node (ref "RAD") (pin "11") (pinfunction "PPAD_11") (pintype "bidirectional"))
      (node (ref "RAD") (pin "17") (pinfunction "V-_17") (pintype "bidirectional"))
      (node (ref "RAD") (pin "18") (pinfunction "V-_18") (pintype "bidirectional"))
      (node (ref "RAD") (pin "20") (pinfunction "PPAD_20") (pintype "bidirectional"))
      (node (ref "RAD") (pin "TH") (pinfunction "PPADHS_TH") (pintype "bidirectional"))
      (node (ref "SWD") (pin "3") (pinfunction "3_3") (pintype "passive"))
      (node (ref "U3") (pin "4") (pinfunction "V-_4") (pintype "power_in"))
      (node (ref "U4") (pin "4") (pinfunction "V-_4") (pintype "power_in"))
      (node (ref "USB") (pin "5") (pinfunction "5_5") (pintype "passive"))
      (node (ref "USB") (pin "M1") (pinfunction "S1_M1") (pintype "passive"))
      (node (ref "USB") (pin "M2") (pinfunction "S2_M2") (pintype "passive"))
      (node (ref "USB") (pin "M3") (pinfunction "S3_M3") (pintype "passive"))
      (node (ref "USB") (pin "M4") (pinfunction "S4_M4") (pintype "passive"))
      (node (ref "X1") (pin "2") (pinfunction "2_2") (pintype "passive"))
      (node (ref "X1") (pin "4") (pinfunction "4_4") (pintype "passive"))
    )
    (net (code "43") (name "Net-(A-PadA)") (class "Default")
      (node (ref "A") (pin "A") (pinfunction "A_A") (pintype "passive"))
      (node (ref "R7") (pin "1") (pinfunction "1_1") (pintype "passive"))
    )
    (net (code "44") (name "Net-(B-PadA)") (class "Default")
      (node (ref "B") (pin "A") (pinfunction "A_A") (pintype "passive"))
      (node (ref "R8") (pin "1") (pinfunction "1_1") (pintype "passive"))
    )
    (net (code "45") (name "Net-(DVD-Pad3)") (class "Default")
      (node (ref "DVD") (pin "3") (pinfunction "3_3") (pintype "passive"))
      (node (ref "R23") (pin "1") (pinfunction "1_1") (pintype "passive"))
    )
    (net (code "46") (name "Net-(DVD-Pad4)") (class "Default")
      (node (ref "DVD") (pin "4") (pinfunction "4_4") (pintype "passive"))
      (node (ref "R23") (pin "2") (pinfunction "2_2") (pintype "passive"))
    )
    (net (code "47") (name "Net-(FOC-CLSET)") (class "Default")
      (node (ref "FOC") (pin "3") (pinfunction "CLSET_3") (pintype "bidirectional"))
      (node (ref "R14") (pin "1") (pinfunction "1_1") (pintype "passive"))
    )
    (net (code "48") (name "Net-(FOC-EN)") (class "Default")
      (node (ref "FOC") (pin "7") (pinfunction "THFLAG_7") (pintype "bidirectional"))
      (node (ref "FOC") (pin "8") (pinfunction "EN_8") (pintype "bidirectional"))
    )
    (net (code "49") (name "Net-(FOC-IN+)") (class "Default")
      (node (ref "FOC") (pin "6") (pinfunction "IN+_6") (pintype "bidirectional"))
      (node (ref "R10") (pin "1") (pinfunction "1_1") (pintype "passive"))
      (node (ref "R20") (pin "2") (pinfunction "2_2") (pintype "passive"))
    )
    (net (code "50") (name "Net-(IC2-NR)") (class "Default")
      (node (ref "C4") (pin "1") (pinfunction "1_1") (pintype "passive"))
      (node (ref "IC2") (pin "4") (pinfunction "NR_4") (pintype "passive"))
    )
    (net (code "51") (name "Net-(IC3-EN)") (class "Default")
      (node (ref "C7") (pin "1") (pinfunction "1_1") (pintype "passive"))
      (node (ref "C9") (pin "1") (pinfunction "1_1") (pintype "passive"))
      (node (ref "IC3") (pin "1") (pinfunction "IN_1") (pintype "power_in"))
      (node (ref "IC3") (pin "3") (pinfunction "EN_3") (pintype "passive"))
      (node (ref "L1") (pin "2") (pinfunction "2_2") (pintype "passive"))
    )
    (net (code "52") (name "Net-(IC3-NR)") (class "Default")
      (node (ref "C6") (pin "1") (pinfunction "1_1") (pintype "passive"))
      (node (ref "IC3") (pin "4") (pinfunction "NR_4") (pintype "passive"))
    )
    (net (code "53") (name "Net-(IC5-IN)") (class "Default")
      (node (ref "C30") (pin "1") (pinfunction "1_1") (pintype "passive"))
      (node (ref "IC5") (pin "1") (pinfunction "IN_1") (pintype "power_in"))
      (node (ref "IC5") (pin "3") (pinfunction "ON_3") (pintype "passive"))
      (node (ref "L2") (pin "2") (pinfunction "2_2") (pintype "passive"))
    )
    (net (code "54") (name "Net-(PWR-PadA)") (class "Default")
      (node (ref "PWR") (pin "A") (pinfunction "A_A") (pintype "passive"))
      (node (ref "R9") (pin "1") (pinfunction "1_1") (pintype "passive"))
    )
    (net (code "55") (name "Net-(R1-Pad2)") (class "Default")
      (node (ref "R1") (pin "2") (pinfunction "2_2") (pintype "passive"))
      (node (ref "USB") (pin "2") (pinfunction "2_2") (pintype "passive"))
    )
    (net (code "56") (name "Net-(R2-Pad2)") (class "Default")
      (node (ref "R2") (pin "2") (pinfunction "2_2") (pintype "passive"))
      (node (ref "USB") (pin "3") (pinfunction "3_3") (pintype "passive"))
    )
    (net (code "57") (name "Net-(RAD-CLSET)") (class "Default")
      (node (ref "R13") (pin "1") (pinfunction "1_1") (pintype "passive"))
      (node (ref "RAD") (pin "3") (pinfunction "CLSET_3") (pintype "bidirectional"))
    )
    (net (code "58") (name "Net-(RAD-EN)") (class "Default")
      (node (ref "RAD") (pin "7") (pinfunction "THFLAG_7") (pintype "bidirectional"))
      (node (ref "RAD") (pin "8") (pinfunction "EN_8") (pintype "bidirectional"))
    )
    (net (code "59") (name "Net-(RAD-IN+)") (class "Default")
      (node (ref "R19") (pin "2") (pinfunction "2_2") (pintype "passive"))
      (node (ref "RAD") (pin "6") (pinfunction "IN+_6") (pintype "bidirectional"))
    )
    (net (code "60") (name "Net-(U3A-+IN)") (class "Default")
      (node (ref "R18") (pin "1") (pinfunction "1_1") (pintype "passive"))
      (node (ref "R33") (pin "1") (pinfunction "1_1") (pintype "passive"))
      (node (ref "U3") (pin "3") (pinfunction "+IN_3") (pintype "input"))
    )
    (net (code "61") (name "Net-(U3A--IN)") (class "Default")
      (node (ref "R12") (pin "1") (pinfunction "1_1") (pintype "passive"))
      (node (ref "U3") (pin "2") (pinfunction "-IN_2") (pintype "input"))
    )
    (net (code "62") (name "Net-(U3A-OUT)") (class "Default")
      (node (ref "R12") (pin "2") (pinfunction "2_2") (pintype "passive"))
      (node (ref "R29") (pin "1") (pinfunction "1_1") (pintype "passive"))
      (node (ref "U3") (pin "1") (pinfunction "OUT_1") (pintype "output"))
    )
    (net (code "63") (name "Net-(U3B-+IN)") (class "Default")
      (node (ref "R17") (pin "1") (pinfunction "1_1") (pintype "passive"))
      (node (ref "R32") (pin "1") (pinfunction "1_1") (pintype "passive"))
      (node (ref "U3") (pin "5") (pinfunction "+IN_5") (pintype "input"))
    )
    (net (code "64") (name "Net-(U3B--IN)") (class "Default")
      (node (ref "R11") (pin "1") (pinfunction "1_1") (pintype "passive"))
      (node (ref "U3") (pin "6") (pinfunction "-IN_6") (pintype "input"))
    )
    (net (code "65") (name "Net-(U3B-OUT)") (class "Default")
      (node (ref "R11") (pin "2") (pinfunction "2_2") (pintype "passive"))
      (node (ref "R28") (pin "1") (pinfunction "1_1") (pintype "passive"))
      (node (ref "U3") (pin "7") (pinfunction "OUT_7") (pintype "output"))
    )
    (net (code "66") (name "Net-(U4A-+IN)") (class "Default")
      (node (ref "R27") (pin "1") (pinfunction "1_1") (pintype "passive"))
      (node (ref "R35") (pin "1") (pinfunction "1_1") (pintype "passive"))
      (node (ref "U4") (pin "3") (pinfunction "+IN_3") (pintype "input"))
    )
    (net (code "67") (name "Net-(U4A--IN)") (class "Default")
      (node (ref "R16") (pin "1") (pinfunction "1_1") (pintype "passive"))
      (node (ref "U4") (pin "2") (pinfunction "-IN_2") (pintype "input"))
    )
    (net (code "68") (name "Net-(U4A-OUT)") (class "Default")
      (node (ref "R16") (pin "2") (pinfunction "2_2") (pintype "passive"))
      (node (ref "R31") (pin "1") (pinfunction "1_1") (pintype "passive"))
      (node (ref "U4") (pin "1") (pinfunction "OUT_1") (pintype "output"))
    )
    (net (code "69") (name "Net-(U4B-+IN)") (class "Default")
      (node (ref "R26") (pin "1") (pinfunction "1_1") (pintype "passive"))
      (node (ref "R34") (pin "1") (pinfunction "1_1") (pintype "passive"))
      (node (ref "U4") (pin "5") (pinfunction "+IN_5") (pintype "input"))
    )
    (net (code "70") (name "Net-(U4B--IN)") (class "Default")
      (node (ref "R15") (pin "1") (pinfunction "1_1") (pintype "passive"))
      (node (ref "U4") (pin "6") (pinfunction "-IN_6") (pintype "input"))
    )
    (net (code "71") (name "Net-(U4B-OUT)") (class "Default")
      (node (ref "R15") (pin "2") (pinfunction "2_2") (pintype "passive"))
      (node (ref "R30") (pin "1") (pinfunction "1_1") (pintype "passive"))
      (node (ref "U4") (pin "7") (pinfunction "OUT_7") (pintype "output"))
    )
    (net (code "72") (name "VCC") (class "Default")
      (node (ref "C12") (pin "+") (pinfunction "+_+") (pintype "passive"))
      (node (ref "C25") (pin "1") (pinfunction "1_1") (pintype "passive"))
      (node (ref "DC7V5") (pin "1") (pinfunction "1_1") (pintype "passive"))
      (node (ref "IC4") (pin "1") (pinfunction "VI_1") (pintype "input"))
      (node (ref "L2") (pin "1") (pinfunction "1_1") (pintype "passive"))
      (node (ref "POWER") (pin "1") (pinfunction "1_1") (pintype "passive"))
    )
    (net (code "73") (name "unconnected-(DC7V5-Pad2)") (class "Default")
      (node (ref "DC7V5") (pin "2") (pinfunction "2_2") (pintype "passive"))
    )
    (net (code "74") (name "unconnected-(DVD-Pad7)") (class "Default")
      (node (ref "DVD") (pin "7") (pinfunction "7_7") (pintype "passive"))
    )
    (net (code "75") (name "unconnected-(DVD-Pad8)") (class "Default")
      (node (ref "DVD") (pin "8") (pinfunction "8_8") (pintype "passive"))
    )
    (net (code "76") (name "unconnected-(DVD-Pad9)") (class "Default")
      (node (ref "DVD") (pin "9") (pinfunction "9_9") (pintype "passive"))
    )
    (net (code "77") (name "unconnected-(DVD-Pad10)") (class "Default")
      (node (ref "DVD") (pin "10") (pinfunction "10_10") (pintype "passive"))
    )
    (net (code "78") (name "unconnected-(DVD-Pad11)") (class "Default")
      (node (ref "DVD") (pin "11") (pinfunction "11_11") (pintype "passive"))
    )
    (net (code "79") (name "unconnected-(DVD-Pad12)") (class "Default")
      (node (ref "DVD") (pin "12") (pinfunction "12_12") (pintype "passive"))
    )
    (net (code "80") (name "unconnected-(DVD-Pad13)") (class "Default")
      (node (ref "DVD") (pin "13") (pinfunction "13_13") (pintype "passive"))
    )
    (net (code "81") (name "unconnected-(DVD-Pad14)") (class "Default")
      (node (ref "DVD") (pin "14") (pinfunction "14_14") (pintype "passive"))
    )
    (net (code "82") (name "unconnected-(DVD-Pad15)") (class "Default")
      (node (ref "DVD") (pin "15") (pinfunction "15_15") (pintype "passive"))
    )
    (net (code "83") (name "unconnected-(DVD-Pad16)") (class "Default")
      (node (ref "DVD") (pin "16") (pinfunction "16_16") (pintype "passive"))
    )
    (net (code "84") (name "unconnected-(DVD-Pad17)") (class "Default")
      (node (ref "DVD") (pin "17") (pinfunction "17_17") (pintype "passive"))
    )
    (net (code "85") (name "unconnected-(DVD-Pad18)") (class "Default")
      (node (ref "DVD") (pin "18") (pinfunction "18_18") (pintype "passive"))
    )
    (net (code "86") (name "unconnected-(DVD-Pad19)") (class "Default")
      (node (ref "DVD") (pin "19") (pinfunction "19_19") (pintype "passive"))
    )
    (net (code "87") (name "unconnected-(DVD-Pad20)") (class "Default")
      (node (ref "DVD") (pin "20") (pinfunction "20_20") (pintype "passive"))
    )
    (net (code "88") (name "unconnected-(DVD-Pad21)") (class "Default")
      (node (ref "DVD") (pin "21") (pinfunction "21_21") (pintype "passive"))
    )
    (net (code "89") (name "unconnected-(DVD-Pad22)") (class "Default")
      (node (ref "DVD") (pin "22") (pinfunction "22_22") (pintype "passive"))
    )
    (net (code "90") (name "unconnected-(DVD-Pad23)") (class "Default")
      (node (ref "DVD") (pin "23") (pinfunction "23_23") (pintype "passive"))
    )
    (net (code "91") (name "unconnected-(DVD-Pad24)") (class "Default")
      (node (ref "DVD") (pin "24") (pinfunction "24_24") (pintype "passive"))
    )
    (net (code "92") (name "unconnected-(DVD-Pad25)") (class "Default")
      (node (ref "DVD") (pin "25") (pinfunction "25_25") (pintype "passive"))
    )
    (net (code "93") (name "unconnected-(DVD-Pad26)") (class "Default")
      (node (ref "DVD") (pin "26") (pinfunction "26_26") (pintype "passive"))
    )
    (net (code "94") (name "unconnected-(DVD-Pad27)") (class "Default")
      (node (ref "DVD") (pin "27") (pinfunction "27_27") (pintype "passive"))
    )
    (net (code "95") (name "unconnected-(DVD-Pad28)") (class "Default")
      (node (ref "DVD") (pin "28") (pinfunction "28_28") (pintype "passive"))
    )
    (net (code "96") (name "unconnected-(DVD-Pad29)") (class "Default")
      (node (ref "DVD") (pin "29") (pinfunction "29_29") (pintype "passive"))
    )
    (net (code "97") (name "unconnected-(DVD-Pad31)") (class "Default")
      (node (ref "DVD") (pin "31") (pinfunction "31_31") (pintype "passive"))
    )
    (net (code "98") (name "unconnected-(DVD-Pad32)") (class "Default")
      (node (ref "DVD") (pin "32") (pinfunction "32_32") (pintype "passive"))
    )
    (net (code "99") (name "unconnected-(DVD-Pad37)") (class "Default")
      (node (ref "DVD") (pin "37") (pinfunction "37_37") (pintype "passive"))
    )
    (net (code "100") (name "unconnected-(DVD-Pad38)") (class "Default")
      (node (ref "DVD") (pin "38") (pinfunction "38_38") (pintype "passive"))
    )
    (net (code "101") (name "unconnected-(DVD-Pad43)") (class "Default")
      (node (ref "DVD") (pin "43") (pinfunction "43_43") (pintype "passive"))
    )
    (net (code "102") (name "unconnected-(DVD-Pad44)") (class "Default")
      (node (ref "DVD") (pin "44") (pinfunction "44_44") (pintype "passive"))
    )
    (net (code "103") (name "unconnected-(FOC-CLFLAG-Pad4)") (class "Default")
      (node (ref "FOC") (pin "4") (pinfunction "CLFLAG_4") (pintype "bidirectional"))
    )
    (net (code "104") (name "unconnected-(FOC-IMON-Pad19)") (class "Default")
      (node (ref "FOC") (pin "19") (pinfunction "IMON_19") (pintype "bidirectional"))
    )
    (net (code "105") (name "unconnected-(FOC-POUT1-Pad2)") (class "Default")
      (node (ref "FOC") (pin "2") (pinfunction "POUT1_2") (pintype "bidirectional"))
    )
    (net (code "106") (name "unconnected-(FOC-POUT2-Pad9)") (class "Default")
      (node (ref "FOC") (pin "9") (pinfunction "POUT2_9") (pintype "bidirectional"))
    )
    (net (code "107") (name "unconnected-(IC1B-PA8-Pad29)") (class "Default")
      (node (ref "IC1") (pin "29") (pinfunction "PA8_29") (pintype "bidirectional"))
    )
    (net (code "108") (name "unconnected-(IC1C-PA1{slash}ADC1_CH2-Pad11)") (class "Default")
      (node (ref "IC1") (pin "11") (pinfunction "PA1/ADC1_CH2_11") (pintype "bidirectional"))
    )
    (net (code "109") (name "unconnected-(IC1C-PA2{slash}ADC1_CH3-Pad12)") (class "Default")
      (node (ref "IC1") (pin "12") (pinfunction "PA2/ADC1_CH3_12") (pintype "bidirectional"))
    )
    (net (code "110") (name "unconnected-(IC1C-PA3{slash}ADC1_CH4-Pad13)") (class "Default")
      (node (ref "IC1") (pin "13") (pinfunction "PA3/ADC1_CH4_13") (pintype "bidirectional"))
    )
    (net (code "111") (name "unconnected-(IC1C-PA7{slash}ADC2_CH4-Pad17)") (class "Default")
      (node (ref "IC1") (pin "17") (pinfunction "PA7/ADC2_CH4_17") (pintype "bidirectional"))
    )
    (net (code "112") (name "unconnected-(IC1D-TIM2_CH3{slash}PB10-Pad21)") (class "Default")
      (node (ref "IC1") (pin "21") (pinfunction "TIM2_CH3/PB10_21") (pintype "bidirectional"))
    )
    (net (code "113") (name "unconnected-(IC1D-TIM2_CH4{slash}PB11-Pad22)") (class "Default")
      (node (ref "IC1") (pin "22") (pinfunction "TIM2_CH4/PB11_22") (pintype "bidirectional"))
    )
    (net (code "114") (name "unconnected-(IC1D-TIM4_CH3{slash}PB8-Pad45)") (class "Default")
      (node (ref "IC1") (pin "45") (pinfunction "TIM4_CH3/PB8_45") (pintype "bidirectional"))
    )
    (net (code "115") (name "unconnected-(IC1D-TIM4_CH4{slash}PB9-Pad46)") (class "Default")
      (node (ref "IC1") (pin "46") (pinfunction "TIM4_CH4/PB9_46") (pintype "bidirectional"))
    )
    (net (code "116") (name "unconnected-(IC1E-PB2-Pad20)") (class "Default")
      (node (ref "IC1") (pin "20") (pinfunction "PB2_20") (pintype "bidirectional"))
    )
    (net (code "117") (name "unconnected-(IC1E-TIM3_CH3{slash}PB0-Pad18)") (class "Default")
      (node (ref "IC1") (pin "18") (pinfunction "TIM3_CH3/PB0_18") (pintype "bidirectional"))
    )
    (net (code "118") (name "unconnected-(IC1E-TIM3_CH4{slash}PB1-Pad19)") (class "Default")
      (node (ref "IC1") (pin "19") (pinfunction "TIM3_CH4/PB1_19") (pintype "bidirectional"))
    )
    (net (code "119") (name "unconnected-(IC1F-PC13-Pad2)") (class "Default")
      (node (ref "IC1") (pin "2") (pinfunction "PC13_2") (pintype "bidirectional"))
    )
    (net (code "120") (name "unconnected-(IC1F-PC14-Pad3)") (class "Default")
      (node (ref "IC1") (pin "3") (pinfunction "PC14_3") (pintype "bidirectional"))
    )
    (net (code "121") (name "unconnected-(IC1F-PC15-Pad4)") (class "Default")
      (node (ref "IC1") (pin "4") (pinfunction "PC15_4") (pintype "bidirectional"))
    )
    (net (code "122") (name "unconnected-(RAD-CLFLAG-Pad4)") (class "Default")
      (node (ref "RAD") (pin "4") (pinfunction "CLFLAG_4") (pintype "bidirectional"))
    )
    (net (code "123") (name "unconnected-(RAD-IMON-Pad19)") (class "Default")
      (node (ref "RAD") (pin "19") (pinfunction "IMON_19") (pintype "bidirectional"))
    )
    (net (code "124") (name "unconnected-(RAD-POUT1-Pad2)") (class "Default")
      (node (ref "RAD") (pin "2") (pinfunction "POUT1_2") (pintype "bidirectional"))
    )
    (net (code "125") (name "unconnected-(RAD-POUT2-Pad9)") (class "Default")
      (node (ref "RAD") (pin "9") (pinfunction "POUT2_9") (pintype "bidirectional"))
    )
    (net (code "126") (name "unconnected-(USB-Pad4)") (class "Default")
      (node (ref "USB") (pin "4") (pinfunction "4_4") (pintype "passive"))
    )
  )
)
